# MS3100_DRV_V0_1.net
KiCad netlist of a schematic drawn in Altium Designer
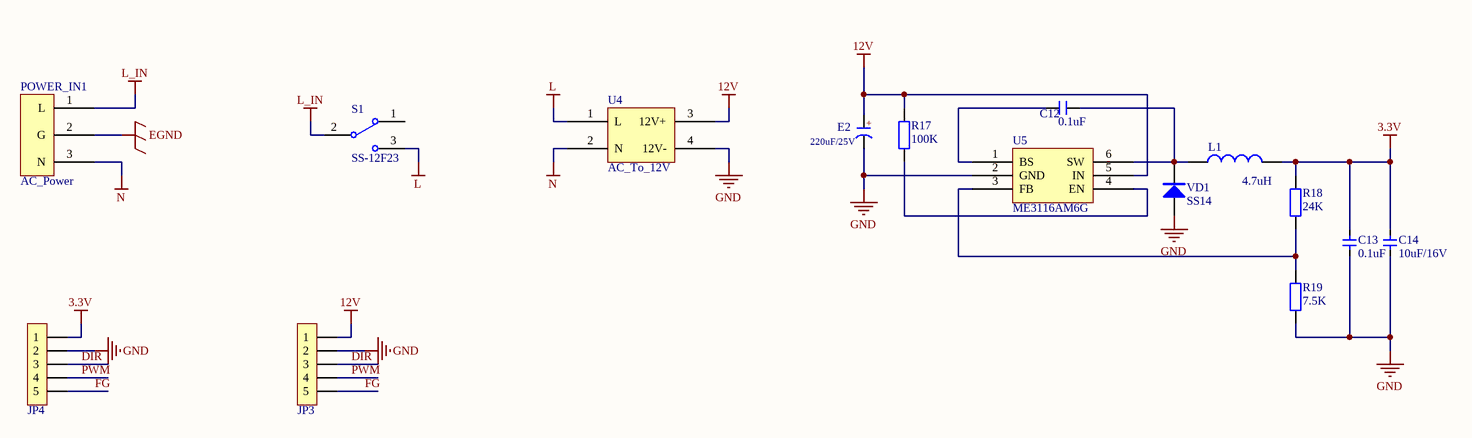
[diagram p0: MS3100_DRV_V0.1.SchDoc]

(export (version "E")
  (design (tool "Eeschema 10.0.6"))
  (components
    (comp (ref "C12")
      (value "0.1uF")
      (footprint "C 0603")
      (description "无极性贴片电容")
      (fields (field (name "版权归属") "源创客"))
      (libsource (lib "电容") (part "C"))
    )
    (comp (ref "C13")
      (value "0.1uF")
      (footprint "C 0603")
      (description "无极性贴片电容")
      (fields (field (name "版权归属") "源创客"))
      (libsource (lib "") (part "C_1"))
    )
    (comp (ref "C14")
      (value "10uF/16V")
      (footprint "C 0805")
      (description "无极性贴片电容")
      (fields (field (name "版权归属") "源创客"))
      (libsource (lib "") (part "C_1"))
    )
    (comp (ref "E2")
      (value "220uF/25V")
      (footprint "CAP 2.5*6.3*11.2 - BK")
      (description "直插电解电容")
      (fields (field (name "版权归属") "源创客"))
      (libsource (lib "电容") (part "C-CAP"))
    )
    (comp (ref "JP3")
      (value "HDR-1X5")
      (footprint "XH2.54-5P")
      (description "5P接插件")
      (fields (field (name "版权归属") "源创客"))
      (libsource (lib "排针-排母") (part "Header 5"))
    )
    (comp (ref "JP4")
      (value "HDR-1X5")
      (footprint "XH2.54-5P")
      (description "5P接插件")
      (fields (field (name "版权归属") "源创客"))
      (libsource (lib "排针-排母") (part "Header 5"))
    )
    (comp (ref "L1")
      (value "4.7uH")
      (footprint "CD32")
      (description "小功率贴片电感")
      (fields (field (name "版权归属") "源创客"))
      (libsource (lib "电感") (part "L"))
    )
    (comp (ref "POWER_IN1")
      (value "AC_Power")
      (footprint "POWER_M")
      (description "AC电源插座")
      (libsource (lib "接口类") (part "AC_Power"))
    )
    (comp (ref "R17")
      (value "100K")
      (footprint "R 0603")
      (description "贴片电阻")
      (fields (field (name "版权归属") "源创客"))
      (libsource (lib "电阻") (part "R"))
    )
    (comp (ref "R18")
      (value "24K")
      (footprint "R 0603")
      (description "贴片电阻")
      (fields (field (name "版权归属") "源创客"))
      (libsource (lib "电阻") (part "R"))
    )
    (comp (ref "R19")
      (value "7.5K")
      (footprint "R 0603")
      (description "贴片电阻")
      (fields (field (name "版权归属") "源创客"))
      (libsource (lib "电阻") (part "R"))
    )
    (comp (ref "S1")
      (value "SS-12F23")
      (footprint "SS11-BBIWJ-R20-R")
      (description "1路波动开关")
      (fields (field (name "版权归属") "源创客"))
      (libsource (lib "开关") (part "SSW-1P"))
    )
    (comp (ref "U4")
      (value "AC_To_12V")
      (footprint "ACTo12V0.5A")
      (description "220V转12V降压模块")
      (libsource (lib "变压器") (part "AC_To_12V"))
    )
    (comp (ref "U5")
      (value "ME3116AM6G")
      (footprint "ME3116AM6G")
      (description "DC-DC电源芯片  24-40V->5V")
      (libsource (lib "变压器") (part "ME3116AM6G"))
    )
    (comp (ref "VD1")
      (value "SS14")
      (footprint "SMA")
      (description "肖特基二极管")
      (fields (field (name "版权归属") "源创客"))
      (libsource (lib "二极管-整流桥") (part "SS14"))
    )
  )
  (nets
    (net (code "1") (name "/DIR") (class "Default")
      (node (ref "JP3") (pin "3") (pinfunction "3_3") (pintype "passive"))
      (node (ref "JP4") (pin "3") (pinfunction "3_3") (pintype "passive"))
    )
    (net (code "2") (name "/FG") (class "Default")
      (node (ref "JP3") (pin "5") (pinfunction "5_5") (pintype "passive"))
      (node (ref "JP4") (pin "5") (pinfunction "5_5") (pintype "passive"))
    )
    (net (code "3") (name "/PWM") (class "Default")
      (node (ref "JP3") (pin "4") (pinfunction "4_4") (pintype "passive"))
      (node (ref "JP4") (pin "4") (pinfunction "4_4") (pintype "passive"))
    )
    (net (code "4") (name "3.3V") (class "Default")
      (node (ref "C13") (pin "2") (pinfunction "2_2") (pintype "passive"))
      (node (ref "C14") (pin "2") (pinfunction "2_2") (pintype "passive"))
      (node (ref "JP4") (pin "1") (pinfunction "1_1") (pintype "passive"))
      (node (ref "L1") (pin "2") (pinfunction "2_2") (pintype "passive"))
      (node (ref "R18") (pin "2") (pinfunction "2_2") (pintype "passive"))
    )
    (net (code "5") (name "12V") (class "Default")
      (node (ref "E2") (pin "1") (pinfunction "A_1") (pintype "passive"))
      (node (ref "JP3") (pin "1") (pinfunction "1_1") (pintype "passive"))
      (node (ref "R17") (pin "2") (pinfunction "2_2") (pintype "passive"))
      (node (ref "U4") (pin "3") (pinfunction "12V+_3") (pintype "passive"))
      (node (ref "U5") (pin "5") (pinfunction "IN_5") (pintype "passive"))
    )
    (net (code "6") (name "EGND") (class "Default")
      (node (ref "POWER_IN1") (pin "2") (pinfunction "G_2") (pintype "passive"))
    )
    (net (code "7") (name "GND") (class "Default")
      (node (ref "C13") (pin "1") (pinfunction "1_1") (pintype "passive"))
      (node (ref "C14") (pin "1") (pinfunction "1_1") (pintype "passive"))
      (node (ref "E2") (pin "2") (pinfunction "K_2") (pintype "passive"))
      (node (ref "JP3") (pin "2") (pinfunction "2_2") (pintype "passive"))
      (node (ref "JP4") (pin "2") (pinfunction "2_2") (pintype "passive"))
      (node (ref "R19") (pin "1") (pinfunction "1_1") (pintype "passive"))
      (node (ref "U4") (pin "4") (pinfunction "12V-_4") (pintype "passive"))
      (node (ref "U5") (pin "2") (pinfunction "GND_2") (pintype "passive"))
      (node (ref "VD1") (pin "1") (pinfunction "A_1") (pintype "passive"))
    )
    (net (code "8") (name "L") (class "Default")
      (node (ref "S1") (pin "3") (pinfunction "3_3") (pintype "passive"))
      (node (ref "U4") (pin "1") (pinfunction "L_1") (pintype "passive"))
    )
    (net (code "9") (name "L_IN") (class "Default")
      (node (ref "POWER_IN1") (pin "1") (pinfunction "L_1") (pintype "passive"))
      (node (ref "S1") (pin "2") (pinfunction "2_2") (pintype "passive"))
    )
    (net (code "10") (name "N") (class "Default")
      (node (ref "POWER_IN1") (pin "3") (pinfunction "N_3") (pintype "passive"))
      (node (ref "U4") (pin "2") (pinfunction "N_2") (pintype "passive"))
    )
    (net (code "11") (name "Net-(U5-BS)") (class "Default")
      (node (ref "C12") (pin "1") (pinfunction "1_1") (pintype "passive"))
      (node (ref "U5") (pin "1") (pinfunction "BS_1") (pintype "passive"))
    )
    (net (code "12") (name "Net-(U5-EN)") (class "Default")
      (node (ref "R17") (pin "1") (pinfunction "1_1") (pintype "passive"))
      (node (ref "U5") (pin "4") (pinfunction "EN_4") (pintype "passive"))
    )
    (net (code "13") (name "Net-(U5-FB)") (class "Default")
      (node (ref "R18") (pin "1") (pinfunction "1_1") (pintype "passive"))
      (node (ref "R19") (pin "2") (pinfunction "2_2") (pintype "passive"))
      (node (ref "U5") (pin "3") (pinfunction "FB_3") (pintype "passive"))
    )
    (net (code "14") (name "Net-(U5-SW)") (class "Default")
      (node (ref "C12") (pin "2") (pinfunction "2_2") (pintype "passive"))
      (node (ref "L1") (pin "1") (pinfunction "1_1") (pintype "passive"))
      (node (ref "U5") (pin "6") (pinfunction "SW_6") (pintype "passive"))
      (node (ref "VD1") (pin "2") (pinfunction "K_2") (pintype "passive"))
    )
    (net (code "15") (name "unconnected-(S1-Pad1)") (class "Default")
      (node (ref "S1") (pin "1") (pinfunction "1_1") (pintype "passive"))
    )
  )
)
